# 5V_Switch.net
KiCad netlist of a schematic drawn in Altium Designer
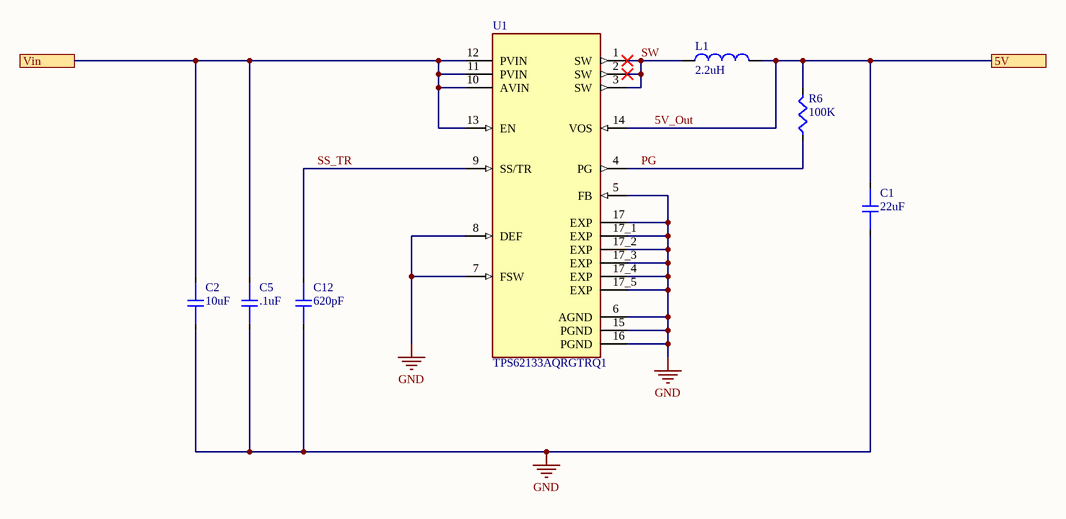
[diagram p0: 5V_Switch.SchDoc]

(export (version "E")
  (design (tool "Eeschema 10.0.6"))
  (components
    (comp (ref "C1")
      (value "22uF")
      (footprint "C0603")
      (description "CAP CER 22UF 10V X5R 0603")
      (fields (field (name "TOLERANCE") "20%"))
      (libsource (lib "SwitchingSupply") (part "C1608X5R1A226M080AC"))
    )
    (comp (ref "C2")
      (value "10uF")
      (footprint "C0603")
      (description "CAP CER 10UF 25V X5R 0603")
      (fields (field (name "TOLERANCE") "20%"))
      (libsource (lib "SwitchingSupply") (part "C1608X5R1E106M080AC"))
    )
    (comp (ref "C5")
      (value ".1uF")
      (footprint "C0402")
      (description "CAP CER 0.1UF 16V X7R 0402")
      (fields (field (name "TOLERANCE") "20%"))
      (libsource (lib "SwitchingSupply") (part "GRM155R71C104KA88D"))
    )
    (comp (ref "C12")
      (value "620pF")
      (footprint "C0402")
      (description "CAP CER 620PF 25V C0G/NP0 0402")
      (fields (field (name "TOLERANCE") "20%"))
      (libsource (lib "SwitchingSupply") (part "GRM1555C1E621JA01D"))
    )
    (comp (ref "L1")
      (value "2.2uH")
      (footprint "74438357022")
      (description "INDUCTOR, 2.2UH, 5.2A, 20%, SHIELDED")
      (fields (field (name "TOLERANCE") "20%"))
      (libsource (lib "SwitchingSupply") (part "74438357022"))
    )
    (comp (ref "R6")
      (value "100K")
      (footprint "C0402")
      (description "RES SMD 100K OHM 1% 1/16W 0402")
      (fields (field (name "TOLERANCE") "20%"))
      (libsource (lib "SwitchingSupply") (part "CRCW0402100KFKED"))
    )
    (comp (ref "U1")
      (value "TPS62133AQRGTRQ1")
      (footprint "QFN50P300X300X100-17N")
      (description "Buck Switching Regulator IC Positive Fixed 5V 1 Output 3A 16-VFQFN Exposed Pad")
      (fields (field (name "MF") "Texas Instruments"))
      (libsource (lib "SwitchingSupply") (part "TPS62133AQRGTRQ1"))
    )
  )
  (nets
    (net (code "1") (name "/5V_Out") (class "Default")
      (node (ref "C1") (pin "2") (pinfunction "2_2") (pintype "passive"))
      (node (ref "L1") (pin "2") (pinfunction "2_2") (pintype "passive"))
      (node (ref "R6") (pin "1") (pinfunction "1_1") (pintype "passive"))
      (node (ref "U1") (pin "14") (pinfunction "VOS_14") (pintype "input"))
    )
    (net (code "2") (name "/PG") (class "Default")
      (node (ref "R6") (pin "2") (pinfunction "2_2") (pintype "passive"))
      (node (ref "U1") (pin "4") (pinfunction "PG_4") (pintype "output"))
    )
    (net (code "3") (name "/SS_TR") (class "Default")
      (node (ref "C12") (pin "2") (pinfunction "2_2") (pintype "passive"))
      (node (ref "U1") (pin "9") (pinfunction "SS/TR_9") (pintype "input"))
    )
    (net (code "4") (name "/SW") (class "Default")
      (node (ref "L1") (pin "1") (pinfunction "1_1") (pintype "passive"))
      (node (ref "U1") (pin "1") (pinfunction "SW_1") (pintype "output"))
      (node (ref "U1") (pin "2") (pinfunction "SW_2") (pintype "output"))
      (node (ref "U1") (pin "3") (pinfunction "SW_3") (pintype "output"))
    )
    (net (code "5") (name "/Vin") (class "Default")
      (node (ref "C2") (pin "2") (pinfunction "2_2") (pintype "passive"))
      (node (ref "C5") (pin "2") (pinfunction "2_2") (pintype "passive"))
      (node (ref "U1") (pin "10") (pinfunction "AVIN_10") (pintype "power_in"))
      (node (ref "U1") (pin "11") (pinfunction "PVIN_11") (pintype "power_in"))
      (node (ref "U1") (pin "12") (pinfunction "PVIN_12") (pintype "power_in"))
      (node (ref "U1") (pin "13") (pinfunction "EN_13") (pintype "input"))
    )
    (net (code "6") (name "GND") (class "Default")
      (node (ref "C1") (pin "1") (pinfunction "1_1") (pintype "passive"))
      (node (ref "C12") (pin "1") (pinfunction "1_1") (pintype "passive"))
      (node (ref "C2") (pin "1") (pinfunction "1_1") (pintype "passive"))
      (node (ref "C5") (pin "1") (pinfunction "1_1") (pintype "passive"))
      (node (ref "U1") (pin "15") (pinfunction "PGND_15") (pintype "power_in"))
      (node (ref "U1") (pin "16") (pinfunction "PGND_16") (pintype "power_in"))
      (node (ref "U1") (pin "17") (pinfunction "EXP_17") (pintype "passive"))
      (node (ref "U1") (pin "17_1") (pinfunction "EXP_17_1") (pintype "passive"))
      (node (ref "U1") (pin "17_2") (pinfunction "EXP_17_2") (pintype "passive"))
      (node (ref "U1") (pin "17_3") (pinfunction "EXP_17_3") (pintype "passive"))
      (node (ref "U1") (pin "17_4") (pinfunction "EXP_17_4") (pintype "passive"))
      (node (ref "U1") (pin "17_5") (pinfunction "EXP_17_5") (pintype "passive"))
      (node (ref "U1") (pin "5") (pinfunction "FB_5") (pintype "input"))
      (node (ref "U1") (pin "6") (pinfunction "AGND_6") (pintype "power_in"))
      (node (ref "U1") (pin "7") (pinfunction "FSW_7") (pintype "input"))
      (node (ref "U1") (pin "8") (pinfunction "DEF_8") (pintype "input"))
    )
  )
)
